# Sheet1.net
KiCad netlist of a schematic drawn in Altium Designer
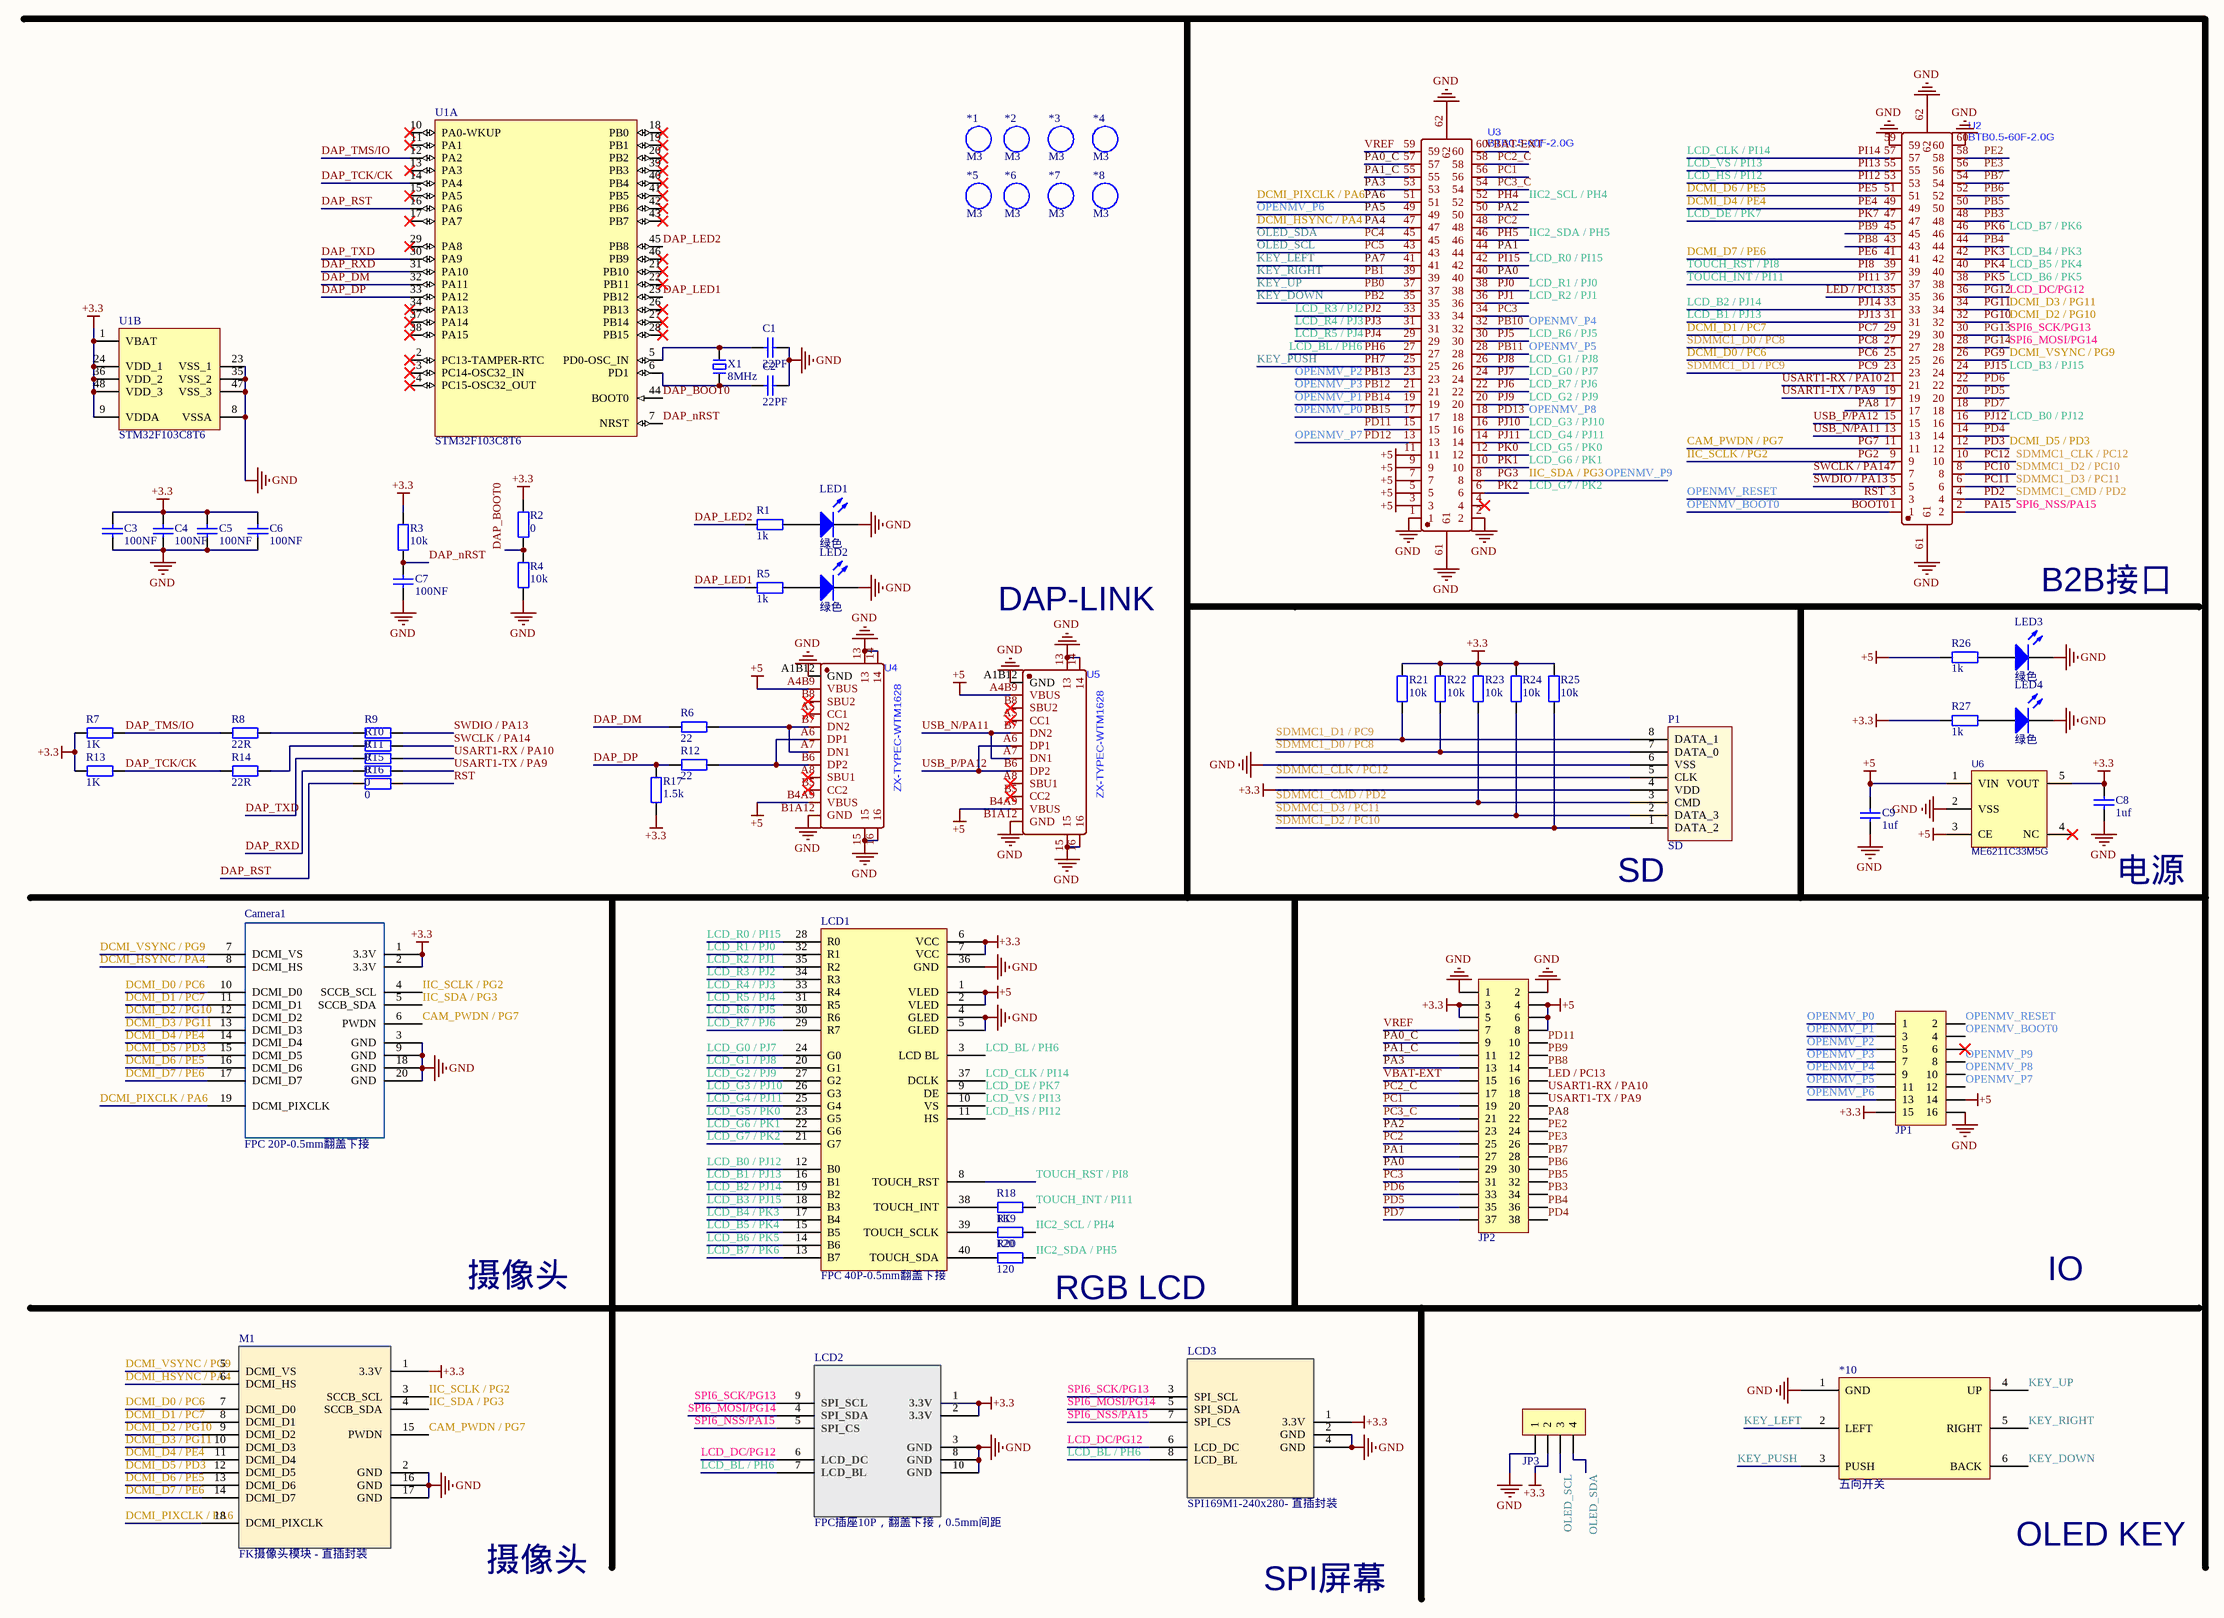
[diagram p0: Sheet1.SchDoc]

(export (version "E")
  (design (tool "Eeschema 10.0.6"))
  (components
    (comp (ref "*1")
      (value "M3")
      (footprint "PCB1:M3 125X200")
      (description "铜柱孔")
      (libsource (lib "STM32H750底板") (part "M3"))
    )
    (comp (ref "*2")
      (value "M3")
      (footprint "PCB1:M3 125X200")
      (description "铜柱孔")
      (libsource (lib "STM32H750底板") (part "M3"))
    )
    (comp (ref "*3")
      (value "M3")
      (footprint "PCB1:M3 125X200")
      (description "铜柱孔")
      (libsource (lib "STM32H750底板") (part "M3"))
    )
    (comp (ref "*4")
      (value "M3")
      (footprint "PCB1:M3 125X200")
      (description "铜柱孔")
      (libsource (lib "STM32H750底板") (part "M3"))
    )
    (comp (ref "*5")
      (value "M3")
      (footprint "PCB1:M3 125X200")
      (description "铜柱孔")
      (libsource (lib "STM32H750底板") (part "M3"))
    )
    (comp (ref "*6")
      (value "M3")
      (footprint "PCB1:M3 125X200")
      (description "铜柱孔")
      (libsource (lib "STM32H750底板") (part "M3"))
    )
    (comp (ref "*7")
      (value "M3")
      (footprint "PCB1:M3 125X200")
      (description "铜柱孔")
      (libsource (lib "STM32H750底板") (part "M3"))
    )
    (comp (ref "*8")
      (value "M3")
      (footprint "PCB1:M3 125X200")
      (description "铜柱孔")
      (libsource (lib "STM32H750底板") (part "M3"))
    )
    (comp (ref "*10")
      (value "五向开关")
      (footprint "PCB1:PCBComponent_1 - duplicate")
      (libsource (lib "STM32H750底板") (part "五向开关"))
    )
    (comp (ref "C1")
      (value "22PF")
      (footprint "PCB1:C0603_L")
      (description "贴片电容/MLCC电容")
      (libsource (lib "STM32H750底板") (part "C"))
    )
    (comp (ref "C2")
      (value "22PF")
      (footprint "PCB1:C0603_L")
      (description "贴片电容/MLCC电容")
      (libsource (lib "STM32H750底板") (part "C"))
    )
    (comp (ref "C3")
      (value "100NF")
      (footprint "PCB1:C0603_L")
      (description "贴片电容/MLCC电容")
      (libsource (lib "STM32H750底板") (part "C"))
    )
    (comp (ref "C4")
      (value "100NF")
      (footprint "PCB1:C0603_L")
      (description "贴片电容/MLCC电容")
      (libsource (lib "STM32H750底板") (part "C"))
    )
    (comp (ref "C5")
      (value "100NF")
      (footprint "PCB1:C0603_L")
      (description "贴片电容/MLCC电容")
      (libsource (lib "STM32H750底板") (part "C"))
    )
    (comp (ref "C6")
      (value "100NF")
      (footprint "PCB1:C0603_L")
      (description "贴片电容/MLCC电容")
      (libsource (lib "STM32H750底板") (part "C"))
    )
    (comp (ref "C7")
      (value "100NF")
      (footprint "PCB1:C0603_L")
      (description "贴片电容/MLCC电容")
      (libsource (lib "STM32H750底板") (part "C"))
    )
    (comp (ref "C8")
      (value "1uf")
      (footprint "PCB1:C0603_L")
      (description "贴片电容/MLCC电容")
      (libsource (lib "STM32H750底板") (part "C"))
    )
    (comp (ref "C9")
      (value "1uf")
      (footprint "PCB1:C0603_L")
      (description "贴片电容/MLCC电容")
      (libsource (lib "STM32H750底板") (part "C"))
    )
    (comp (ref "Camera1")
      (value "FPC 20P-0.5mm翻盖下接")
      (footprint "PCB1:FPC20P-0.5MM")
      (libsource (lib "STM32H750底板") (part "FK_Camera"))
    )
    (comp (ref "JP1")
      (value "Header 8X2")
      (footprint "PCB1:HDR2.54-LI-2x8P")
      (description "8*2P接插件")
      (libsource (lib "STM32H750底板") (part "Header 8X2"))
    )
    (comp (ref "JP2")
      (value "Header 2X11")
      (footprint "PCB1:HDR2.54-LI-2x19P")
      (description "19*2P接插件")
      (libsource (lib "STM32H750底板") (part "Header 19X2"))
    )
    (comp (ref "JP3")
      (value "HDR-1X4")
      (footprint "PCB1:HDR2.54-LI-4P")
      (description "4P接插件")
      (libsource (lib "STM32H750底板") (part "Header 4"))
    )
    (comp (ref "LCD1")
      (value "FPC 40P-0.5mm翻盖下接")
      (footprint "PCB1:FPC40P-0.5MM")
      (libsource (lib "STM32H750底板") (part "MY-RGB"))
    )
    (comp (ref "LCD2")
      (value "FPC插座10P，翻盖下接，0.5mm间距")
      (footprint "PCB1:FPC10P-0.5MM")
      (libsource (lib "STM32H750底板") (part "LCD-SPI"))
    )
    (comp (ref "LCD3")
      (value "SPI169M1-240x280- 直插封装")
      (footprint "PCB1:SPI169M1-240x280 - 直插封装")
      (libsource (lib "STM32H750底板") (part "SPI169M1-240x280- 直插封装"))
    )
    (comp (ref "LED1")
      (value "绿色")
      (footprint "PCB1:LED0805_G")
      (description "贴片LED")
      (libsource (lib "STM32H750底板") (part "LED"))
    )
    (comp (ref "LED2")
      (value "绿色")
      (footprint "PCB1:LED0805_G")
      (description "贴片LED")
      (libsource (lib "STM32H750底板") (part "LED"))
    )
    (comp (ref "LED3")
      (value "绿色")
      (footprint "PCB1:LED0805_G")
      (description "贴片LED")
      (libsource (lib "STM32H750底板") (part "LED"))
    )
    (comp (ref "LED4")
      (value "绿色")
      (footprint "PCB1:LED0805_G")
      (description "贴片LED")
      (libsource (lib "STM32H750底板") (part "LED"))
    )
    (comp (ref "M1") (value "FK摄像头模块 - 直插封装") (libsource (lib "STM32H750底板") (part "FK摄像头模块 - 直插封装")))
    (comp (ref "P1")
      (value "SD")
      (footprint "PCB1:MICRO SD")
      (description "自弹式TF卡座")
      (libsource (lib "STM32H750底板") (part "Micro SD_SD"))
    )
    (comp (ref "R1")
      (value "1k")
      (footprint "PCB1:R0603_L")
      (description "贴片电阻")
      (libsource (lib "STM32H750底板") (part "R"))
    )
    (comp (ref "R2")
      (value "0")
      (footprint "PCB1:R0603_L")
      (description "贴片电阻")
      (libsource (lib "STM32H750底板") (part "R"))
    )
    (comp (ref "R3")
      (value "10k")
      (footprint "PCB1:R0603_L")
      (description "贴片电阻")
      (libsource (lib "STM32H750底板") (part "R"))
    )
    (comp (ref "R4")
      (value "10k")
      (footprint "PCB1:R0603_L")
      (description "贴片电阻")
      (libsource (lib "STM32H750底板") (part "R"))
    )
    (comp (ref "R5")
      (value "1k")
      (footprint "PCB1:R0603_L")
      (description "贴片电阻")
      (libsource (lib "STM32H750底板") (part "R"))
    )
    (comp (ref "R6")
      (value "22")
      (footprint "PCB1:R0402_L")
      (description "贴片电阻")
      (libsource (lib "STM32H750底板") (part "R"))
    )
    (comp (ref "R7")
      (value "1K")
      (footprint "PCB1:R0603_L")
      (description "贴片电阻")
      (libsource (lib "STM32H750底板") (part "R"))
    )
    (comp (ref "R8")
      (value "22R")
      (footprint "PCB1:R0603_L")
      (description "贴片电阻")
      (libsource (lib "STM32H750底板") (part "R"))
    )
    (comp (ref "R9")
      (value "0")
      (footprint "PCB1:R0603_L")
      (description "贴片电阻")
      (libsource (lib "STM32H750底板") (part "R"))
    )
    (comp (ref "R10")
      (value "0")
      (footprint "PCB1:R0603_L")
      (description "贴片电阻")
      (libsource (lib "STM32H750底板") (part "R"))
    )
    (comp (ref "R11")
      (value "0")
      (footprint "PCB1:R0603_L")
      (description "贴片电阻")
      (libsource (lib "STM32H750底板") (part "R"))
    )
    (comp (ref "R12")
      (value "22")
      (footprint "PCB1:R0402_L")
      (description "贴片电阻")
      (libsource (lib "STM32H750底板") (part "R"))
    )
    (comp (ref "R13")
      (value "1K")
      (footprint "PCB1:R0603_L")
      (description "贴片电阻")
      (libsource (lib "STM32H750底板") (part "R"))
    )
    (comp (ref "R14")
      (value "22R")
      (footprint "PCB1:R0603_L")
      (description "贴片电阻")
      (libsource (lib "STM32H750底板") (part "R"))
    )
    (comp (ref "R15")
      (value "0")
      (footprint "PCB1:R0603_L")
      (description "贴片电阻")
      (libsource (lib "STM32H750底板") (part "R"))
    )
    (comp (ref "R16")
      (value "0")
      (footprint "PCB1:R0603_L")
      (description "贴片电阻")
      (libsource (lib "STM32H750底板") (part "R"))
    )
    (comp (ref "R17")
      (value "1.5k")
      (footprint "PCB1:R0402_L")
      (description "贴片电阻")
      (libsource (lib "STM32H750底板") (part "R"))
    )
    (comp (ref "R18")
      (value "1K")
      (footprint "PCB1:R0603_L")
      (description "贴片电阻")
      (libsource (lib "STM32H750底板") (part "R"))
    )
    (comp (ref "R19")
      (value "120")
      (footprint "PCB1:R0603_L")
      (description "贴片电阻")
      (libsource (lib "STM32H750底板") (part "R"))
    )
    (comp (ref "R20")
      (value "120")
      (footprint "PCB1:R0603_L")
      (description "贴片电阻")
      (libsource (lib "STM32H750底板") (part "R"))
    )
    (comp (ref "R21")
      (value "10k")
      (footprint "PCB1:R0603_L")
      (description "贴片电阻")
      (libsource (lib "STM32H750底板") (part "R"))
    )
    (comp (ref "R22")
      (value "10k")
      (footprint "PCB1:R0603_L")
      (description "贴片电阻")
      (libsource (lib "STM32H750底板") (part "R"))
    )
    (comp (ref "R23")
      (value "10k")
      (footprint "PCB1:R0603_L")
      (description "贴片电阻")
      (libsource (lib "STM32H750底板") (part "R"))
    )
    (comp (ref "R24")
      (value "10k")
      (footprint "PCB1:R0603_L")
      (description "贴片电阻")
      (libsource (lib "STM32H750底板") (part "R"))
    )
    (comp (ref "R25")
      (value "10k")
      (footprint "PCB1:R0603_L")
      (description "贴片电阻")
      (libsource (lib "STM32H750底板") (part "R"))
    )
    (comp (ref "R26")
      (value "1k")
      (footprint "PCB1:R0603_L")
      (description "贴片电阻")
      (libsource (lib "STM32H750底板") (part "R"))
    )
    (comp (ref "R27")
      (value "1k")
      (footprint "PCB1:R0603_L")
      (description "贴片电阻")
      (libsource (lib "STM32H750底板") (part "R"))
    )
    (comp (ref "U1")
      (value "STM32F103C8T6")
      (footprint "PCB1:LQFP48_N")
      (libsource (lib "STM32H750底板") (part "STM32F103C8T6"))
    )
    (comp (ref "U2")
      (value "BTB0.5-60F-2.0G")
      (footprint "PCB1:CONN-SMD_60P-P0.50_BTB0.5-60F-2.0G")
      (libsource (lib "STM32H750底板") (part "BTB0.5-60F-2.0G"))
    )
    (comp (ref "U3")
      (value "BTB0.5-60F-2.0G")
      (footprint "PCB1:CONN-SMD_60P-P0.50_BTB0.5-60F-2.0G")
      (libsource (lib "STM32H750底板") (part "BTB0.5-60F-2.0G"))
    )
    (comp (ref "U4")
      (value "ZX-TYPEC-WTM1628")
      (footprint "PCB1:USB-C-SMD_ZX-TYPEC-WTM1628")
      (libsource (lib "STM32H750底板") (part "ZX-TYPEC-WTM1628"))
    )
    (comp (ref "U5")
      (value "ZX-TYPEC-WTM1628")
      (footprint "PCB1:USB-C-SMD_ZX-TYPEC-WTM1628")
      (libsource (lib "STM32H750底板") (part "ZX-TYPEC-WTM1628"))
    )
    (comp (ref "U6")
      (value "ME6211C33M5G")
      (footprint "PCB1:SOT-23-5")
      (description "LDO 3.3V/0.5A")
      (libsource (lib "STM32H750底板") (part "ME6211C33"))
    )
    (comp (ref "X1")
      (value "8MHz")
      (footprint "PCB1:XTAL-3215-2P")
      (description "2脚无源晶振(谐振器）")
      (libsource (lib "STM32H750底板") (part "XTAL-2P"))
    )
  )
  (nets
    (net (code "1") (name "+3.3") (class "Default")
      (node (ref "C3") (pin "2") (pinfunction "2_2") (pintype "passive"))
      (node (ref "C4") (pin "2") (pinfunction "2_2") (pintype "passive"))
      (node (ref "C5") (pin "2") (pinfunction "2_2") (pintype "passive"))
      (node (ref "C6") (pin "2") (pinfunction "2_2") (pintype "passive"))
      (node (ref "C8") (pin "2") (pinfunction "2_2") (pintype "passive"))
      (node (ref "Camera1") (pin "1") (pinfunction "3.3V_1") (pintype "passive"))
      (node (ref "Camera1") (pin "2") (pinfunction "3.3V_2") (pintype "passive"))
      (node (ref "JP1") (pin "15") (pinfunction "15_15") (pintype "passive"))
      (node (ref "JP2") (pin "3") (pinfunction "3_3") (pintype "passive"))
      (node (ref "JP2") (pin "5") (pinfunction "5_5") (pintype "passive"))
      (node (ref "JP3") (pin "2") (pinfunction "2_2") (pintype "passive"))
      (node (ref "LCD1") (pin "6") (pinfunction "VCC_6") (pintype "passive"))
      (node (ref "LCD1") (pin "7") (pinfunction "VCC_7") (pintype "passive"))
      (node (ref "LCD2") (pin "1") (pinfunction "3.3V_1") (pintype "passive"))
      (node (ref "LCD2") (pin "2") (pinfunction "3.3V_2") (pintype "passive"))
      (node (ref "LCD3") (pin "1") (pinfunction "3.3V_1") (pintype "passive"))
      (node (ref "M1") (pin "1") (pinfunction "3.3V_1") (pintype "passive"))
      (node (ref "P1") (pin "4") (pinfunction "VDD_4") (pintype "passive"))
      (node (ref "R13") (pin "1") (pinfunction "1_1") (pintype "passive"))
      (node (ref "R17") (pin "1") (pinfunction "1_1") (pintype "passive"))
      (node (ref "R2") (pin "2") (pinfunction "2_2") (pintype "passive"))
      (node (ref "R21") (pin "1") (pinfunction "1_1") (pintype "passive"))
      (node (ref "R22") (pin "1") (pinfunction "1_1") (pintype "passive"))
      (node (ref "R23") (pin "1") (pinfunction "1_1") (pintype "passive"))
      (node (ref "R24") (pin "1") (pinfunction "1_1") (pintype "passive"))
      (node (ref "R25") (pin "1") (pinfunction "1_1") (pintype "passive"))
      (node (ref "R27") (pin "1") (pinfunction "1_1") (pintype "passive"))
      (node (ref "R3") (pin "2") (pinfunction "2_2") (pintype "passive"))
      (node (ref "R7") (pin "1") (pinfunction "1_1") (pintype "passive"))
      (node (ref "U1") (pin "1") (pinfunction "VBAT_1") (pintype "power_in"))
      (node (ref "U1") (pin "24") (pinfunction "VDD_1_24") (pintype "power_in"))
      (node (ref "U1") (pin "36") (pinfunction "VDD_2_36") (pintype "power_in"))
      (node (ref "U1") (pin "48") (pinfunction "VDD_3_48") (pintype "power_in"))
      (node (ref "U1") (pin "9") (pinfunction "VDDA_9") (pintype "power_in"))
      (node (ref "U6") (pin "5") (pinfunction "VOUT_5") (pintype "passive"))
    )
    (net (code "2") (name "+5") (class "Default")
      (node (ref "C9") (pin "2") (pinfunction "2_2") (pintype "passive"))
      (node (ref "JP1") (pin "14") (pinfunction "14_14") (pintype "passive"))
      (node (ref "JP2") (pin "4") (pinfunction "4_4") (pintype "passive"))
      (node (ref "JP2") (pin "6") (pinfunction "6_6") (pintype "passive"))
      (node (ref "JP2") (pin "8") (pinfunction "8_8") (pintype "passive"))
      (node (ref "LCD1") (pin "1") (pinfunction "VLED_1") (pintype "passive"))
      (node (ref "LCD1") (pin "2") (pinfunction "VLED_2") (pintype "passive"))
      (node (ref "R26") (pin "1") (pinfunction "1_1") (pintype "passive"))
      (node (ref "U3") (pin "11") (pinfunction "11_11") (pintype "passive"))
      (node (ref "U3") (pin "3") (pinfunction "3_3") (pintype "passive"))
      (node (ref "U3") (pin "5") (pinfunction "5_5") (pintype "passive"))
      (node (ref "U3") (pin "7") (pinfunction "7_7") (pintype "passive"))
      (node (ref "U3") (pin "9") (pinfunction "9_9") (pintype "passive"))
      (node (ref "U4") (pin "A4B9") (pinfunction "VBUS_A4B9") (pintype "passive"))
      (node (ref "U4") (pin "B4A9") (pinfunction "VBUS_B4A9") (pintype "passive"))
      (node (ref "U5") (pin "A4B9") (pinfunction "VBUS_A4B9") (pintype "passive"))
      (node (ref "U5") (pin "B4A9") (pinfunction "VBUS_B4A9") (pintype "passive"))
      (node (ref "U6") (pin "1") (pinfunction "VIN_1") (pintype "passive"))
      (node (ref "U6") (pin "3") (pinfunction "CE_3") (pintype "passive"))
    )
    (net (code "3") (name "/BOOT0") (class "Default")
      (node (ref "JP1") (pin "4") (pinfunction "4_4") (pintype "passive"))
      (node (ref "U2") (pin "1") (pinfunction "1_1") (pintype "passive"))
    )
    (net (code "4") (name "/CAM_PWDN {slash} PG7") (class "Default")
      (node (ref "Camera1") (pin "6") (pinfunction "PWDN_6") (pintype "passive"))
      (node (ref "M1") (pin "15") (pinfunction "PWDN_15") (pintype "passive"))
      (node (ref "U2") (pin "11") (pinfunction "11_11") (pintype "passive"))
    )
    (net (code "5") (name "/DAP_BOOT0") (class "Default")
      (node (ref "R2") (pin "1") (pinfunction "1_1") (pintype "passive"))
      (node (ref "R4") (pin "2") (pinfunction "2_2") (pintype "passive"))
      (node (ref "U1") (pin "44") (pinfunction "BOOT0_44") (pintype "input"))
    )
    (net (code "6") (name "/DAP_DM") (class "Default")
      (node (ref "R6") (pin "1") (pinfunction "1_1") (pintype "passive"))
      (node (ref "U1") (pin "32") (pinfunction "PA11_32") (pintype "bidirectional"))
    )
    (net (code "7") (name "/DAP_DP") (class "Default")
      (node (ref "R12") (pin "1") (pinfunction "1_1") (pintype "passive"))
      (node (ref "R17") (pin "2") (pinfunction "2_2") (pintype "passive"))
      (node (ref "U1") (pin "33") (pinfunction "PA12_33") (pintype "bidirectional"))
    )
    (net (code "8") (name "/DAP_LED1") (class "Default")
      (node (ref "R5") (pin "1") (pinfunction "1_1") (pintype "passive"))
      (node (ref "U1") (pin "25") (pinfunction "PB12_25") (pintype "bidirectional"))
    )
    (net (code "9") (name "/DAP_LED2") (class "Default")
      (node (ref "R1") (pin "1") (pinfunction "1_1") (pintype "passive"))
      (node (ref "U1") (pin "45") (pinfunction "PB8_45") (pintype "bidirectional"))
    )
    (net (code "10") (name "/DAP_RST") (class "Default")
      (node (ref "R16") (pin "1") (pinfunction "1_1") (pintype "passive"))
      (node (ref "U1") (pin "16") (pinfunction "PA6_16") (pintype "bidirectional"))
    )
    (net (code "11") (name "/DAP_RXD") (class "Default")
      (node (ref "R15") (pin "1") (pinfunction "1_1") (pintype "passive"))
      (node (ref "U1") (pin "31") (pinfunction "PA10_31") (pintype "bidirectional"))
    )
    (net (code "12") (name "/DAP_TCK{slash}CK") (class "Default")
      (node (ref "R13") (pin "2") (pinfunction "2_2") (pintype "passive"))
      (node (ref "R14") (pin "1") (pinfunction "1_1") (pintype "passive"))
      (node (ref "U1") (pin "14") (pinfunction "PA4_14") (pintype "bidirectional"))
    )
    (net (code "13") (name "/DAP_TMS{slash}IO") (class "Default")
      (node (ref "R7") (pin "2") (pinfunction "2_2") (pintype "passive"))
      (node (ref "R8") (pin "1") (pinfunction "1_1") (pintype "passive"))
      (node (ref "U1") (pin "12") (pinfunction "PA2_12") (pintype "bidirectional"))
    )
    (net (code "14") (name "/DAP_TXD") (class "Default")
      (node (ref "R11") (pin "1") (pinfunction "1_1") (pintype "passive"))
      (node (ref "U1") (pin "30") (pinfunction "PA9_30") (pintype "bidirectional"))
    )
    (net (code "15") (name "/DAP_nRST") (class "Default")
      (node (ref "C7") (pin "2") (pinfunction "2_2") (pintype "passive"))
      (node (ref "R3") (pin "1") (pinfunction "1_1") (pintype "passive"))
      (node (ref "U1") (pin "7") (pinfunction "NRST_7") (pintype "bidirectional"))
    )
    (net (code "16") (name "/DCMI_D0 {slash} PC6") (class "Default")
      (node (ref "Camera1") (pin "10") (pinfunction "DCMI_D0_10") (pintype "passive"))
      (node (ref "M1") (pin "7") (pinfunction "DCMI_D0_7") (pintype "passive"))
      (node (ref "U2") (pin "25") (pinfunction "25_25") (pintype "passive"))
    )
    (net (code "17") (name "/DCMI_D1 {slash} PC7") (class "Default")
      (node (ref "Camera1") (pin "11") (pinfunction "DCMI_D1_11") (pintype "passive"))
      (node (ref "M1") (pin "8") (pinfunction "DCMI_D1_8") (pintype "passive"))
      (node (ref "U2") (pin "29") (pinfunction "29_29") (pintype "passive"))
    )
    (net (code "18") (name "/DCMI_D2 {slash} PG10") (class "Default")
      (node (ref "Camera1") (pin "12") (pinfunction "DCMI_D2_12") (pintype "passive"))
      (node (ref "M1") (pin "9") (pinfunction "DCMI_D2_9") (pintype "passive"))
      (node (ref "U2") (pin "32") (pinfunction "32_32") (pintype "passive"))
    )
    (net (code "19") (name "/DCMI_D3 {slash} PG11") (class "Default")
      (node (ref "Camera1") (pin "13") (pinfunction "DCMI_D3_13") (pintype "passive"))
      (node (ref "M1") (pin "10") (pinfunction "DCMI_D3_10") (pintype "passive"))
      (node (ref "U2") (pin "34") (pinfunction "34_34") (pintype "passive"))
    )
    (net (code "20") (name "/DCMI_D4 {slash} PE4") (class "Default")
      (node (ref "Camera1") (pin "14") (pinfunction "DCMI_D4_14") (pintype "passive"))
      (node (ref "M1") (pin "11") (pinfunction "DCMI_D4_11") (pintype "passive"))
      (node (ref "U2") (pin "49") (pinfunction "49_49") (pintype "passive"))
    )
    (net (code "21") (name "/DCMI_D5 {slash} PD3") (class "Default")
      (node (ref "Camera1") (pin "15") (pinfunction "DCMI_D5_15") (pintype "passive"))
      (node (ref "M1") (pin "12") (pinfunction "DCMI_D5_12") (pintype "passive"))
      (node (ref "U2") (pin "12") (pinfunction "12_12") (pintype "passive"))
    )
    (net (code "22") (name "/DCMI_D6 {slash} PE5") (class "Default")
      (node (ref "Camera1") (pin "16") (pinfunction "DCMI_D6_16") (pintype "passive"))
      (node (ref "M1") (pin "13") (pinfunction "DCMI_D6_13") (pintype "passive"))
      (node (ref "U2") (pin "51") (pinfunction "51_51") (pintype "passive"))
    )
    (net (code "23") (name "/DCMI_D7 {slash} PE6") (class "Default")
      (node (ref "Camera1") (pin "17") (pinfunction "DCMI_D7_17") (pintype "passive"))
      (node (ref "M1") (pin "14") (pinfunction "DCMI_D7_14") (pintype "passive"))
      (node (ref "U2") (pin "41") (pinfunction "41_41") (pintype "passive"))
    )
    (net (code "24") (name "/DCMI_HSYNC {slash} PA4") (class "Default")
      (node (ref "Camera1") (pin "8") (pinfunction "DCMI_HS_8") (pintype "passive"))
      (node (ref "M1") (pin "6") (pinfunction "DCMI_HS_6") (pintype "passive"))
      (node (ref "U3") (pin "47") (pinfunction "47_47") (pintype "passive"))
    )
    (net (code "25") (name "/DCMI_PIXCLK {slash} PA6") (class "Default")
      (node (ref "Camera1") (pin "19") (pinfunction "DCMI_PIXCLK_19") (pintype "passive"))
      (node (ref "M1") (pin "18") (pinfunction "DCMI_PIXCLK_18") (pintype "passive"))
      (node (ref "U3") (pin "51") (pinfunction "51_51") (pintype "passive"))
    )
    (net (code "26") (name "/DCMI_VSYNC {slash} PG9") (class "Default")
      (node (ref "Camera1") (pin "7") (pinfunction "DCMI_VS_7") (pintype "passive"))
      (node (ref "M1") (pin "5") (pinfunction "DCMI_VS_5") (pintype "passive"))
      (node (ref "U2") (pin "26") (pinfunction "26_26") (pintype "passive"))
    )
    (net (code "27") (name "/IIC2_SCL {slash} PH4") (class "Default")
      (node (ref "R19") (pin "2") (pinfunction "2_2") (pintype "passive"))
      (node (ref "U3") (pin "52") (pinfunction "52_52") (pintype "passive"))
    )
    (net (code "28") (name "/IIC2_SDA {slash} PH5") (class "Default")
      (node (ref "R20") (pin "2") (pinfunction "2_2") (pintype "passive"))
      (node (ref "U3") (pin "46") (pinfunction "46_46") (pintype "passive"))
    )
    (net (code "29") (name "/IIC_SCLK {slash} PG2") (class "Default")
      (node (ref "Camera1") (pin "4") (pinfunction "SCCB_SCL_4") (pintype "passive"))
      (node (ref "M1") (pin "3") (pinfunction "SCCB_SCL_3") (pintype "passive"))
      (node (ref "U2") (pin "9") (pinfunction "9_9") (pintype "passive"))
    )
    (net (code "30") (name "/IIC_SDA {slash} PG3") (class "Default")
      (node (ref "Camera1") (pin "5") (pinfunction "SCCB_SDA_5") (pintype "passive"))
      (node (ref "JP1") (pin "8") (pinfunction "8_8") (pintype "passive"))
      (node (ref "M1") (pin "4") (pinfunction "SCCB_SDA_4") (pintype "passive"))
      (node (ref "U3") (pin "8") (pinfunction "8_8") (pintype "passive"))
    )
    (net (code "31") (name "/KEY_DOWN") (class "Default")
      (node (ref "*10") (pin "6") (pinfunction "BACK_6") (pintype "passive"))
      (node (ref "U3") (pin "35") (pinfunction "35_35") (pintype "passive"))
    )
    (net (code "32") (name "/KEY_LEFT") (class "Default")
      (node (ref "*10") (pin "2") (pinfunction "LEFT_2") (pintype "passive"))
      (node (ref "U3") (pin "41") (pinfunction "41_41") (pintype "passive"))
    )
    (net (code "33") (name "/KEY_PUSH") (class "Default")
      (node (ref "*10") (pin "3") (pinfunction "PUSH_3") (pintype "passive"))
      (node (ref "U3") (pin "25") (pinfunction "25_25") (pintype "passive"))
    )
    (net (code "34") (name "/KEY_RIGHT") (class "Default")
      (node (ref "*10") (pin "5") (pinfunction "RIGHT_5") (pintype "passive"))
      (node (ref "U3") (pin "39") (pinfunction "39_39") (pintype "passive"))
    )
    (net (code "35") (name "/KEY_UP") (class "Default")
      (node (ref "*10") (pin "4") (pinfunction "UP_4") (pintype "passive"))
      (node (ref "U3") (pin "37") (pinfunction "37_37") (pintype "passive"))
    )
    (net (code "36") (name "/LCD_B0 {slash} PJ12") (class "Default")
      (node (ref "LCD1") (pin "12") (pinfunction "B0_12") (pintype "passive"))
      (node (ref "U2") (pin "16") (pinfunction "16_16") (pintype "passive"))
    )
    (net (code "37") (name "/LCD_B1 {slash} PJ13") (class "Default")
      (node (ref "LCD1") (pin "16") (pinfunction "B1_16") (pintype "passive"))
      (node (ref "U2") (pin "31") (pinfunction "31_31") (pintype "passive"))
    )
    (net (code "38") (name "/LCD_B2 {slash} PJ14") (class "Default")
      (node (ref "LCD1") (pin "19") (pinfunction "B2_19") (pintype "passive"))
      (node (ref "U2") (pin "33") (pinfunction "33_33") (pintype "passive"))
    )
    (net (code "39") (name "/LCD_B3 {slash} PJ15") (class "Default")
      (node (ref "LCD1") (pin "18") (pinfunction "B3_18") (pintype "passive"))
      (node (ref "U2") (pin "24") (pinfunction "24_24") (pintype "passive"))
    )
    (net (code "40") (name "/LCD_B4 {slash} PK3") (class "Default")
      (node (ref "LCD1") (pin "17") (pinfunction "B4_17") (pintype "passive"))
      (node (ref "U2") (pin "42") (pinfunction "42_42") (pintype "passive"))
    )
    (net (code "41") (name "/LCD_B5 {slash} PK4") (class "Default")
      (node (ref "LCD1") (pin "15") (pinfunction "B5_15") (pintype "passive"))
      (node (ref "U2") (pin "40") (pinfunction "40_40") (pintype "passive"))
    )
    (net (code "42") (name "/LCD_B6 {slash} PK5") (class "Default")
      (node (ref "LCD1") (pin "14") (pinfunction "B6_14") (pintype "passive"))
      (node (ref "U2") (pin "38") (pinfunction "38_38") (pintype "passive"))
    )
    (net (code "43") (name "/LCD_B7 {slash} PK6") (class "Default")
      (node (ref "LCD1") (pin "13") (pinfunction "B7_13") (pintype "passive"))
      (node (ref "U2") (pin "46") (pinfunction "46_46") (pintype "passive"))
    )
    (net (code "44") (name "/LCD_BL {slash} PH6") (class "Default")
      (node (ref "LCD1") (pin "3") (pinfunction "LCD_BL_3") (pintype "passive"))
      (node (ref "LCD2") (pin "7") (pinfunction "LCD_BL_7") (pintype "passive"))
      (node (ref "LCD3") (pin "8") (pinfunction "LCD_BL_8") (pintype "passive"))
      (node (ref "U3") (pin "27") (pinfunction "27_27") (pintype "passive"))
    )
    (net (code "45") (name "/LCD_CLK {slash} PI14") (class "Default")
      (node (ref "LCD1") (pin "37") (pinfunction "DCLK_37") (pintype "passive"))
      (node (ref "U2") (pin "57") (pinfunction "57_57") (pintype "passive"))
    )
    (net (code "46") (name "/LCD_DC{slash}PG12") (class "Default")
      (node (ref "LCD2") (pin "6") (pinfunction "LCD_DC_6") (pintype "passive"))
      (node (ref "LCD3") (pin "6") (pinfunction "LCD_DC_6") (pintype "passive"))
      (node (ref "U2") (pin "36") (pinfunction "36_36") (pintype "passive"))
    )
    (net (code "47") (name "/LCD_DE {slash} PK7") (class "Default")
      (node (ref "LCD1") (pin "9") (pinfunction "DE_9") (pintype "passive"))
      (node (ref "U2") (pin "47") (pinfunction "47_47") (pintype "passive"))
    )
    (net (code "48") (name "/LCD_G0 {slash} PJ7") (class "Default")
      (node (ref "LCD1") (pin "24") (pinfunction "G0_24") (pintype "passive"))
      (node (ref "U3") (pin "24") (pinfunction "24_24") (pintype "passive"))
    )
    (net (code "49") (name "/LCD_G1 {slash} PJ8") (class "Default")
      (node (ref "LCD1") (pin "20") (pinfunction "G1_20") (pintype "passive"))
      (node (ref "U3") (pin "26") (pinfunction "26_26") (pintype "passive"))
    )
    (net (code "50") (name "/LCD_G2 {slash} PJ9") (class "Default")
      (node (ref "LCD1") (pin "27") (pinfunction "G2_27") (pintype "passive"))
      (node (ref "U3") (pin "20") (pinfunction "20_20") (pintype "passive"))
    )
    (net (code "51") (name "/LCD_G3 {slash} PJ10") (class "Default")
      (node (ref "LCD1") (pin "26") (pinfunction "G3_26") (pintype "passive"))
      (node (ref "U3") (pin "16") (pinfunction "16_16") (pintype "passive"))
    )
    (net (code "52") (name "/LCD_G4 {slash} PJ11") (class "Default")
      (node (ref "LCD1") (pin "25") (pinfunction "G4_25") (pintype "passive"))
      (node (ref "U3") (pin "14") (pinfunction "14_14") (pintype "passive"))
    )
    (net (code "53") (name "/LCD_G5 {slash} PK0") (class "Default")
      (node (ref "LCD1") (pin "23") (pinfunction "G5_23") (pintype "passive"))
      (node (ref "U3") (pin "12") (pinfunction "12_12") (pintype "passive"))
    )
    (net (code "54") (name "/LCD_G6 {slash} PK1") (class "Default")
      (node (ref "LCD1") (pin "22") (pinfunction "G6_22") (pintype "passive"))
      (node (ref "U3") (pin "10") (pinfunction "10_10") (pintype "passive"))
    )
    (net (code "55") (name "/LCD_G7 {slash} PK2") (class "Default")
      (node (ref "LCD1") (pin "21") (pinfunction "G7_21") (pintype "passive"))
      (node (ref "U3") (pin "6") (pinfunction "6_6") (pintype "passive"))
    )
    (net (code "56") (name "/LCD_HS {slash} PI12") (class "Default")
      (node (ref "LCD1") (pin "11") (pinfunction "HS_11") (pintype "passive"))
      (node (ref "U2") (pin "53") (pinfunction "53_53") (pintype "passive"))
    )
    (net (code "57") (name "/LCD_R0 {slash} PI15") (class "Default")
      (node (ref "LCD1") (pin "28") (pinfunction "R0_28") (pintype "passive"))
      (node (ref "U3") (pin "42") (pinfunction "42_42") (pintype "passive"))
    )
    (net (code "58") (name "/LCD_R1 {slash} PJ0") (class "Default")
      (node (ref "LCD1") (pin "32") (pinfunction "R1_32") (pintype "passive"))
      (node (ref "U3") (pin "38") (pinfunction "38_38") (pintype "passive"))
    )
    (net (code "59") (name "/LCD_R2 {slash} PJ1") (class "Default")
      (node (ref "LCD1") (pin "35") (pinfunction "R2_35") (pintype "passive"))
      (node (ref "U3") (pin "36") (pinfunction "36_36") (pintype "passive"))
    )
    (net (code "60") (name "/LCD_R3 {slash} PJ2") (class "Default")
      (node (ref "LCD1") (pin "34") (pinfunction "R3_34") (pintype "passive"))
      (node (ref "U3") (pin "33") (pinfunction "33_33") (pintype "passive"))
    )
    (net (code "61") (name "/LCD_R4 {slash} PJ3") (class "Default")
      (node (ref "LCD1") (pin "33") (pinfunction "R4_33") (pintype "passive"))
      (node (ref "U3") (pin "31") (pinfunction "31_31") (pintype "passive"))
    )
    (net (code "62") (name "/LCD_R5 {slash} PJ4") (class "Default")
      (node (ref "LCD1") (pin "31") (pinfunction "R5_31") (pintype "passive"))
      (node (ref "U3") (pin "29") (pinfunction "29_29") (pintype "passive"))
    )
    (net (code "63") (name "/LCD_R6 {slash} PJ5") (class "Default")
      (node (ref "LCD1") (pin "30") (pinfunction "R6_30") (pintype "passive"))
      (node (ref "U3") (pin "30") (pinfunction "30_30") (pintype "passive"))
    )
    (net (code "64") (name "/LCD_R7 {slash} PJ6") (class "Default")
      (node (ref "LCD1") (pin "29") (pinfunction "R7_29") (pintype "passive"))
      (node (ref "U3") (pin "22") (pinfunction "22_22") (pintype "passive"))
    )
    (net (code "65") (name "/LCD_VS {slash} PI13") (class "Default")
      (node (ref "LCD1") (pin "10") (pinfunction "VS_10") (pintype "passive"))
      (node (ref "U2") (pin "55") (pinfunction "55_55") (pintype "passive"))
    )
    (net (code "66") (name "/LED {slash} PC13") (class "Default")
      (node (ref "JP2") (pin "16") (pinfunction "16_16") (pintype "passive"))
      (node (ref "U2") (pin "35") (pinfunction "35_35") (pintype "passive"))
    )
    (net (code "67") (name "/OLED_SCL") (class "Default")
      (node (ref "JP3") (pin "3") (pinfunction "3_3") (pintype "passive"))
      (node (ref "U3") (pin "43") (pinfunction "43_43") (pintype "passive"))
    )
    (net (code "68") (name "/OLED_SDA") (class "Default")
      (node (ref "JP3") (pin "4") (pinfunction "4_4") (pintype "passive"))
      (node (ref "U3") (pin "45") (pinfunction "45_45") (pintype "passive"))
    )
    (net (code "69") (name "/OPENMV_P0") (class "Default")
      (node (ref "JP1") (pin "1") (pinfunction "1_1") (pintype "passive"))
      (node (ref "U3") (pin "17") (pinfunction "17_17") (pintype "passive"))
    )
    (net (code "70") (name "/OPENMV_P1") (class "Default")
      (node (ref "JP1") (pin "3") (pinfunction "3_3") (pintype "passive"))
      (node (ref "U3") (pin "19") (pinfunction "19_19") (pintype "passive"))
    )
    (net (code "71") (name "/OPENMV_P2") (class "Default")
      (node (ref "JP1") (pin "5") (pinfunction "5_5") (pintype "passive"))
      (node (ref "U3") (pin "23") (pinfunction "23_23") (pintype "passive"))
    )
    (net (code "72") (name "/OPENMV_P3") (class "Default")
      (node (ref "JP1") (pin "7") (pinfunction "7_7") (pintype "passive"))
      (node (ref "U3") (pin "21") (pinfunction "21_21") (pintype "passive"))
    )
    (net (code "73") (name "/OPENMV_P4") (class "Default")
      (node (ref "JP1") (pin "9") (pinfunction "9_9") (pintype "passive"))
      (node (ref "U3") (pin "32") (pinfunction "32_32") (pintype "passive"))
    )
    (net (code "74") (name "/OPENMV_P5") (class "Default")
      (node (ref "JP1") (pin "11") (pinfunction "11_11") (pintype "passive"))
      (node (ref "U3") (pin "28") (pinfunction "28_28") (pintype "passive"))
    )
    (net (code "75") (name "/OPENMV_P6") (class "Default")
      (node (ref "JP1") (pin "13") (pinfunction "13_13") (pintype "passive"))
      (node (ref "U3") (pin "49") (pinfunction "49_49") (pintype "passive"))
    )
    (net (code "76") (name "/OPENMV_P7") (class "Default")
      (node (ref "JP1") (pin "12") (pinfunction "12_12") (pintype "passive"))
      (node (ref "U3") (pin "13") (pinfunction "13_13") (pintype "passive"))
    )
    (net (code "77") (name "/OPENMV_P8") (class "Default")
      (node (ref "JP1") (pin "10") (pinfunction "10_10") (pintype "passive"))
      (node (ref "U3") (pin "18") (pinfunction "18_18") (pintype "passive"))
    )
    (net (code "78") (name "/OPENMV_RESET") (class "Default")
      (node (ref "JP1") (pin "2") (pinfunction "2_2") (pintype "passive"))
      (node (ref "R16") (pin "2") (pinfunction "2_2") (pintype "passive"))
      (node (ref "U2") (pin "3") (pinfunction "3_3") (pintype "passive"))
    )
    (net (code "79") (name "/PA0") (class "Default")
      (node (ref "JP2") (pin "29") (pinfunction "29_29") (pintype "passive"))
      (node (ref "U3") (pin "40") (pinfunction "40_40") (pintype "passive"))
    )
    (net (code "80") (name "/PA0_C") (class "Default")
      (node (ref "JP2") (pin "9") (pinfunction "9_9") (pintype "passive"))
      (node (ref "U3") (pin "57") (pinfunction "57_57") (pintype "passive"))
    )
    (net (code "81") (name "/PA1") (class "Default")
      (node (ref "JP2") (pin "27") (pinfunction "27_27") (pintype "passive"))
      (node (ref "U3") (pin "44") (pinfunction "44_44") (pintype "passive"))
    )
    (net (code "82") (name "/PA1_C") (class "Default")
      (node (ref "JP2") (pin "11") (pinfunction "11_11") (pintype "passive"))
      (node (ref "U3") (pin "55") (pinfunction "55_55") (pintype "passive"))
    )
    (net (code "83") (name "/PA2") (class "Default")
      (node (ref "JP2") (pin "23") (pinfunction "23_23") (pintype "passive"))
      (node (ref "U3") (pin "50") (pinfunction "50_50") (pintype "passive"))
    )
    (net (code "84") (name "/PA3") (class "Default")
      (node (ref "JP2") (pin "13") (pinfunction "13_13") (pintype "passive"))
      (node (ref "U3") (pin "53") (pinfunction "53_53") (pintype "passive"))
    )
    (net (code "85") (name "/PA8") (class "Default")
      (node (ref "JP2") (pin "22") (pinfunction "22_22") (pintype "passive"))
      (node (ref "U2") (pin "17") (pinfunction "17_17") (pintype "passive"))
    )
    (net (code "86") (name "/PA15") (class "Default")
      (node (ref "LCD2") (pin "5") (pinfunction "SPI_CS_5") (pintype "passive"))
      (node (ref "LCD3") (pin "7") (pinfunction "SPI_CS_7") (pintype "passive"))
      (node (ref "U2") (pin "2") (pinfunction "2_2") (pintype "passive"))
    )
    (net (code "87") (name "/PB3") (class "Default")
      (node (ref "JP2") (pin "34") (pinfunction "34_34") (pintype "passive"))
      (node (ref "U2") (pin "48") (pinfunction "48_48") (pintype "passive"))
    )
    (net (code "88") (name "/PB4") (class "Default")
      (node (ref "JP2") (pin "36") (pinfunction "36_36") (pintype "passive"))
      (node (ref "U2") (pin "44") (pinfunction "44_44") (pintype "passive"))
    )
    (net (code "89") (name "/PB5") (class "Default")
      (node (ref "JP2") (pin "32") (pinfunction "32_32") (pintype "passive"))
      (node (ref "U2") (pin "50") (pinfunction "50_50") (pintype "passive"))
    )
    (net (code "90") (name "/PB6") (class "Default")
      (node (ref "JP2") (pin "30") (pinfunction "30_30") (pintype "passive"))
      (node (ref "U2") (pin "52") (pinfunction "52_52") (pintype "passive"))
    )
    (net (code "91") (name "/PB7") (class "Default")
      (node (ref "JP2") (pin "28") (pinfunction "28_28") (pintype "passive"))
      (node (ref "U2") (pin "54") (pinfunction "54_54") (pintype "passive"))
    )
    (net (code "92") (name "/PB8") (class "Default")
      (node (ref "JP2") (pin "14") (pinfunction "14_14") (pintype "passive"))
      (node (ref "U2") (pin "43") (pinfunction "43_43") (pintype "passive"))
    )
    (net (code "93") (name "/PB9") (class "Default")
      (node (ref "JP2") (pin "12") (pinfunction "12_12") (pintype "passive"))
      (node (ref "U2") (pin "45") (pinfunction "45_45") (pintype "passive"))
    )
    (net (code "94") (name "/PC1") (class "Default")
      (node (ref "JP2") (pin "19") (pinfunction "19_19") (pintype "passive"))
      (node (ref "U3") (pin "56") (pinfunction "56_56") (pintype "passive"))
    )
    (net (code "95") (name "/PC2") (class "Default")
      (node (ref "JP2") (pin "25") (pinfunction "25_25") (pintype "passive"))
      (node (ref "U3") (pin "48") (pinfunction "48_48") (pintype "passive"))
    )
    (net (code "96") (name "/PC2_C") (class "Default")
      (node (ref "JP2") (pin "17") (pinfunction "17_17") (pintype "passive"))
      (node (ref "U3") (pin "58") (pinfunction "58_58") (pintype "passive"))
    )
    (net (code "97") (name "/PC3") (class "Default")
      (node (ref "JP2") (pin "31") (pinfunction "31_31") (pintype "passive"))
      (node (ref "U3") (pin "34") (pinfunction "34_34") (pintype "passive"))
    )
    (net (code "98") (name "/PC3_C") (class "Default")
      (node (ref "JP2") (pin "21") (pinfunction "21_21") (pintype "passive"))
      (node (ref "U3") (pin "54") (pinfunction "54_54") (pintype "passive"))
    )
    (net (code "99") (name "/PC8") (class "Default")
      (node (ref "P1") (pin "7") (pinfunction "DATA_0_7") (pintype "passive"))
      (node (ref "R22") (pin "2") (pinfunction "2_2") (pintype "passive"))
      (node (ref "U2") (pin "27") (pinfunction "27_27") (pintype "passive"))
    )
    (net (code "100") (name "/PC9") (class "Default")
      (node (ref "P1") (pin "8") (pinfunction "DATA_1_8") (pintype "passive"))
      (node (ref "R21") (pin "2") (pinfunction "2_2") (pintype "passive"))
      (node (ref "U2") (pin "23") (pinfunction "23_23") (pintype "passive"))
    )
    (net (code "101") (name "/PC10") (class "Default")
      (node (ref "P1") (pin "1") (pinfunction "DATA_2_1") (pintype "passive"))
      (node (ref "R25") (pin "2") (pinfunction "2_2") (pintype "passive"))
      (node (ref "U2") (pin "8") (pinfunction "8_8") (pintype "passive"))
    )
    (net (code "102") (name "/PC11") (class "Default")
      (node (ref "P1") (pin "2") (pinfunction "DATA_3_2") (pintype "passive"))
      (node (ref "R24") (pin "2") (pinfunction "2_2") (pintype "passive"))
      (node (ref "U2") (pin "6") (pinfunction "6_6") (pintype "passive"))
    )
    (net (code "103") (name "/PC12") (class "Default")
      (node (ref "P1") (pin "5") (pinfunction "CLK_5") (pintype "passive"))
      (node (ref "U2") (pin "10") (pinfunction "10_10") (pintype "passive"))
    )
    (net (code "104") (name "/PD2") (class "Default")
      (node (ref "P1") (pin "3") (pinfunction "CMD_3") (pintype "passive"))
      (node (ref "R23") (pin "2") (pinfunction "2_2") (pintype "passive"))
      (node (ref "U2") (pin "4") (pinfunction "4_4") (pintype "passive"))
    )
    (net (code "105") (name "/PD4") (class "Default")
      (node (ref "JP2") (pin "38") (pinfunction "38_38") (pintype "passive"))
      (node (ref "U2") (pin "14") (pinfunction "14_14") (pintype "passive"))
    )
    (net (code "106") (name "/PD5") (class "Default")
      (node (ref "JP2") (pin "35") (pinfunction "35_35") (pintype "passive"))
      (node (ref "U2") (pin "20") (pinfunction "20_20") (pintype "passive"))
    )
    (net (code "107") (name "/PD6") (class "Default")
      (node (ref "JP2") (pin "33") (pinfunction "33_33") (pintype "passive"))
      (node (ref "U2") (pin "22") (pinfunction "22_22") (pintype "passive"))
    )
    (net (code "108") (name "/PD7") (class "Default")
      (node (ref "JP2") (pin "37") (pinfunction "37_37") (pintype "passive"))
      (node (ref "U2") (pin "18") (pinfunction "18_18") (pintype "passive"))
    )
    (net (code "109") (name "/PD11") (class "Default")
      (node (ref "JP2") (pin "10") (pinfunction "10_10") (pintype "passive"))
      (node (ref "U3") (pin "15") (pinfunction "15_15") (pintype "passive"))
    )
    (net (code "110") (name "/PE2") (class "Default")
      (node (ref "JP2") (pin "24") (pinfunction "24_24") (pintype "passive"))
      (node (ref "U2") (pin "58") (pinfunction "58_58") (pintype "passive"))
    )
    (net (code "111") (name "/PE3") (class "Default")
      (node (ref "JP2") (pin "26") (pinfunction "26_26") (pintype "passive"))
      (node (ref "U2") (pin "56") (pinfunction "56_56") (pintype "passive"))
    )
    (net (code "112") (name "/PG13") (class "Default")
      (node (ref "LCD2") (pin "9") (pinfunction "SPI_SCL_9") (pintype "passive"))
      (node (ref "LCD3") (pin "3") (pinfunction "SPI_SCL_3") (pintype "passive"))
      (node (ref "U2") (pin "30") (pinfunction "30_30") (pintype "passive"))
    )
    (net (code "113") (name "/PG14") (class "Default")
      (node (ref "LCD2") (pin "4") (pinfunction "SPI_SDA_4") (pintype "passive"))
      (node (ref "LCD3") (pin "5") (pinfunction "SPI_SDA_5") (pintype "passive"))
      (node (ref "U2") (pin "28") (pinfunction "28_28") (pintype "passive"))
    )
    (net (code "114") (name "/PI8") (class "Default")
      (node (ref "LCD1") (pin "8") (pinfunction "TOUCH_RST_8") (pintype "passive"))
      (node (ref "U2") (pin "39") (pinfunction "39_39") (pintype "passive"))
    )
    (net (code "115") (name "/PI11") (class "Default")
      (node (ref "R18") (pin "2") (pinfunction "2_2") (pintype "passive"))
      (node (ref "U2") (pin "37") (pinfunction "37_37") (pintype "passive"))
    )
    (net (code "116") (name "/SWCLK {slash} PA14") (class "Default")
      (node (ref "R10") (pin "2") (pinfunction "2_2") (pintype "passive"))
      (node (ref "U2") (pin "7") (pinfunction "7_7") (pintype "passive"))
    )
    (net (code "117") (name "/SWDIO {slash} PA13") (class "Default")
      (node (ref "R9") (pin "2") (pinfunction "2_2") (pintype "passive"))
      (node (ref "U2") (pin "5") (pinfunction "5_5") (pintype "passive"))
    )
    (net (code "118") (name "/USART1-RX {slash} PA10") (class "Default")
      (node (ref "JP2") (pin "18") (pinfunction "18_18") (pintype "passive"))
      (node (ref "R11") (pin "2") (pinfunction "2_2") (pintype "passive"))
      (node (ref "U2") (pin "21") (pinfunction "21_21") (pintype "passive"))
    )
    (net (code "119") (name "/USART1-TX {slash} PA9") (class "Default")
      (node (ref "JP2") (pin "20") (pinfunction "20_20") (pintype "passive"))
      (node (ref "R15") (pin "2") (pinfunction "2_2") (pintype "passive"))
      (node (ref "U2") (pin "19") (pinfunction "19_19") (pintype "passive"))
    )
    (net (code "120") (name "/USB_N{slash}PA11") (class "Default")
      (node (ref "U2") (pin "13") (pinfunction "13_13") (pintype "passive"))
      (node (ref "U5") (pin "A7") (pinfunction "DN1_A7") (pintype "passive"))
      (node (ref "U5") (pin "B7") (pinfunction "DN2_B7") (pintype "passive"))
    )
    (net (code "121") (name "/USB_P{slash}PA12") (class "Default")
      (node (ref "U2") (pin "15") (pinfunction "15_15") (pintype "passive"))
      (node (ref "U5") (pin "A6") (pinfunction "DP1_A6") (pintype "passive"))
      (node (ref "U5") (pin "B6") (pinfunction "DP2_B6") (pintype "passive"))
    )
    (net (code "122") (name "/VBAT-EXT") (class "Default")
      (node (ref "JP2") (pin "15") (pinfunction "15_15") (pintype "passive"))
      (node (ref "U3") (pin "60") (pinfunction "60_60") (pintype "passive"))
    )
    (net (code "123") (name "/VREF") (class "Default")
      (node (ref "JP2") (pin "7") (pinfunction "7_7") (pintype "passive"))
      (node (ref "U3") (pin "59") (pinfunction "59_59") (pintype "passive"))
    )
    (net (code "124") (name "GND") (class "Default")
      (node (ref "*10") (pin "1") (pinfunction "GND_1") (pintype "passive"))
      (node (ref "C1") (pin "2") (pinfunction "2_2") (pintype "passive"))
      (node (ref "C2") (pin "2") (pinfunction "2_2") (pintype "passive"))
      (node (ref "C3") (pin "1") (pinfunction "1_1") (pintype "passive"))
      (node (ref "C4") (pin "1") (pinfunction "1_1") (pintype "passive"))
      (node (ref "C5") (pin "1") (pinfunction "1_1") (pintype "passive"))
      (node (ref "C6") (pin "1") (pinfunction "1_1") (pintype "passive"))
      (node (ref "C7") (pin "1") (pinfunction "1_1") (pintype "passive"))
      (node (ref "C8") (pin "1") (pinfunction "1_1") (pintype "passive"))
      (node (ref "C9") (pin "1") (pinfunction "1_1") (pintype "passive"))
      (node (ref "Camera1") (pin "18") (pinfunction "GND_18") (pintype "passive"))
      (node (ref "Camera1") (pin "20") (pinfunction "GND_20") (pintype "passive"))
      (node (ref "Camera1") (pin "3") (pinfunction "GND_3") (pintype "passive"))
      (node (ref "Camera1") (pin "9") (pinfunction "GND_9") (pintype "passive"))
      (node (ref "JP1") (pin "16") (pinfunction "16_16") (pintype "passive"))
      (node (ref "JP2") (pin "1") (pinfunction "1_1") (pintype "passive"))
      (node (ref "JP2") (pin "2") (pinfunction "2_2") (pintype "passive"))
      (node (ref "JP3") (pin "1") (pinfunction "1_1") (pintype "passive"))
      (node (ref "LCD1") (pin "36") (pinfunction "GND_36") (pintype "passive"))
      (node (ref "LCD1") (pin "4") (pinfunction "GLED_4") (pintype "passive"))
      (node (ref "LCD1") (pin "5") (pinfunction "GLED_5") (pintype "passive"))
      (node (ref "LCD2") (pin "10") (pinfunction "GND_10") (pintype "passive"))
      (node (ref "LCD2") (pin "3") (pinfunction "GND_3") (pintype "passive"))
      (node (ref "LCD2") (pin "8") (pinfunction "GND_8") (pintype "passive"))
      (node (ref "LCD3") (pin "2") (pinfunction "GND_2") (pintype "passive"))
      (node (ref "LCD3") (pin "4") (pinfunction "GND_4") (pintype "passive"))
      (node (ref "LED1") (pin "2") (pinfunction "K_2") (pintype "passive"))
      (node (ref "LED2") (pin "2") (pinfunction "K_2") (pintype "passive"))
      (node (ref "LED3") (pin "2") (pinfunction "K_2") (pintype "passive"))
      (node (ref "LED4") (pin "2") (pinfunction "K_2") (pintype "passive"))
      (node (ref "M1") (pin "16") (pinfunction "GND_16") (pintype "passive"))
      (node (ref "M1") (pin "17") (pinfunction "GND_17") (pintype "passive"))
      (node (ref "M1") (pin "2") (pinfunction "GND_2") (pintype "passive"))
      (node (ref "P1") (pin "6") (pinfunction "VSS_6") (pintype "passive"))
      (node (ref "R4") (pin "1") (pinfunction "1_1") (pintype "passive"))
      (node (ref "U1") (pin "23") (pinfunction "VSS_1_23") (pintype "power_in"))
      (node (ref "U1") (pin "35") (pinfunction "VSS_2_35") (pintype "power_in"))
      (node (ref "U1") (pin "47") (pinfunction "VSS_3_47") (pintype "power_in"))
      (node (ref "U1") (pin "8") (pinfunction "VSSA_8") (pintype "power_in"))
      (node (ref "U2") (pin "59") (pinfunction "59_59") (pintype "passive"))
      (node (ref "U2") (pin "60") (pinfunction "60_60") (pintype "passive"))
      (node (ref "U2") (pin "61") (pinfunction "61_61") (pintype "passive"))
      (node (ref "U2") (pin "62") (pinfunction "62_62") (pintype "passive"))
      (node (ref "U3") (pin "1") (pinfunction "1_1") (pintype "passive"))
      (node (ref "U3") (pin "2") (pinfunction "2_2") (pintype "passive"))
      (node (ref "U3") (pin "61") (pinfunction "61_61") (pintype "passive"))
      (node (ref "U3") (pin "62") (pinfunction "62_62") (pintype "passive"))
      (node (ref "U4") (pin "13") (pinfunction "13_13") (pintype "passive"))
      (node (ref "U4") (pin "14") (pinfunction "14_14") (pintype "passive"))
      (node (ref "U4") (pin "15") (pinfunction "15_15") (pintype "passive"))
      (node (ref "U4") (pin "16") (pinfunction "16_16") (pintype "passive"))
      (node (ref "U4") (pin "A1B12") (pinfunction "GND_A1B12") (pintype "passive"))
      (node (ref "U4") (pin "B1A12") (pinfunction "GND_B1A12") (pintype "passive"))
      (node (ref "U5") (pin "13") (pinfunction "13_13") (pintype "passive"))
      (node (ref "U5") (pin "14") (pinfunction "14_14") (pintype "passive"))
      (node (ref "U5") (pin "15") (pinfunction "15_15") (pintype "passive"))
      (node (ref "U5") (pin "16") (pinfunction "16_16") (pintype "passive"))
      (node (ref "U5") (pin "A1B12") (pinfunction "GND_A1B12") (pintype "passive"))
      (node (ref "U5") (pin "B1A12") (pinfunction "GND_B1A12") (pintype "passive"))
      (node (ref "U6") (pin "2") (pinfunction "VSS_2") (pintype "passive"))
    )
    (net (code "125") (name "Net-(LCD1-TOUCH_INT)") (class "Default")
      (node (ref "LCD1") (pin "38") (pinfunction "TOUCH_INT_38") (pintype "passive"))
      (node (ref "R18") (pin "1") (pinfunction "1_1") (pintype "passive"))
    )
    (net (code "126") (name "Net-(LCD1-TOUCH_SCLK)") (class "Default")
      (node (ref "LCD1") (pin "39") (pinfunction "TOUCH_SCLK_39") (pintype "passive"))
      (node (ref "R19") (pin "1") (pinfunction "1_1") (pintype "passive"))
    )
    (net (code "127") (name "Net-(LCD1-TOUCH_SDA)") (class "Default")
      (node (ref "LCD1") (pin "40") (pinfunction "TOUCH_SDA_40") (pintype "passive"))
      (node (ref "R20") (pin "1") (pinfunction "1_1") (pintype "passive"))
    )
    (net (code "128") (name "Net-(LED1-A)") (class "Default")
      (node (ref "LED1") (pin "1") (pinfunction "A_1") (pintype "passive"))
      (node (ref "R1") (pin "2") (pinfunction "2_2") (pintype "passive"))
    )
    (net (code "129") (name "Net-(LED2-A)") (class "Default")
      (node (ref "LED2") (pin "1") (pinfunction "A_1") (pintype "passive"))
      (node (ref "R5") (pin "2") (pinfunction "2_2") (pintype "passive"))
    )
    (net (code "130") (name "Net-(LED3-A)") (class "Default")
      (node (ref "LED3") (pin "1") (pinfunction "A_1") (pintype "passive"))
      (node (ref "R26") (pin "2") (pinfunction "2_2") (pintype "passive"))
    )
    (net (code "131") (name "Net-(LED4-A)") (class "Default")
      (node (ref "LED4") (pin "1") (pinfunction "A_1") (pintype "passive"))
      (node (ref "R27") (pin "2") (pinfunction "2_2") (pintype "passive"))
    )
    (net (code "132") (name "Net-(R8-Pad2)") (class "Default")
      (node (ref "R8") (pin "2") (pinfunction "2_2") (pintype "passive"))
      (node (ref "R9") (pin "1") (pinfunction "1_1") (pintype "passive"))
    )
    (net (code "133") (name "Net-(R10-Pad1)") (class "Default")
      (node (ref "R10") (pin "1") (pinfunction "1_1") (pintype "passive"))
      (node (ref "R14") (pin "2") (pinfunction "2_2") (pintype "passive"))
    )
    (net (code "134") (name "Net-(U1A-PD0-OSC_IN)") (class "Default")
      (node (ref "C1") (pin "1") (pinfunction "1_1") (pintype "passive"))
      (node (ref "U1") (pin "5") (pinfunction "PD0-OSC_IN_5") (pintype "bidirectional"))
      (node (ref "X1") (pin "1") (pinfunction "1_1") (pintype "passive"))
    )
    (net (code "135") (name "Net-(U1A-PD1)") (class "Default")
      (node (ref "C2") (pin "1") (pinfunction "1_1") (pintype "passive"))
      (node (ref "U1") (pin "6") (pinfunction "PD1_6") (pintype "bidirectional"))
      (node (ref "X1") (pin "2") (pinfunction "2_2") (pintype "passive"))
    )
    (net (code "136") (name "Net-(U4-DN1)") (class "Default")
      (node (ref "R6") (pin "2") (pinfunction "2_2") (pintype "passive"))
      (node (ref "U4") (pin "A7") (pinfunction "DN1_A7") (pintype "passive"))
      (node (ref "U4") (pin "B7") (pinfunction "DN2_B7") (pintype "passive"))
    )
    (net (code "137") (name "Net-(U4-DP1)") (class "Default")
      (node (ref "R12") (pin "2") (pinfunction "2_2") (pintype "passive"))
      (node (ref "U4") (pin "A6") (pinfunction "DP1_A6") (pintype "passive"))
      (node (ref "U4") (pin "B6") (pinfunction "DP2_B6") (pintype "passive"))
    )
    (net (code "138") (name "unconnected-(JP1-Pad6)") (class "Default")
      (node (ref "JP1") (pin "6") (pinfunction "6_6") (pintype "passive+no_connect"))
    )
    (net (code "139") (name "unconnected-(U1A-PA0-WKUP-Pad10)") (class "Default")
      (node (ref "U1") (pin "10") (pinfunction "PA0-WKUP_10") (pintype "bidirectional+no_connect"))
    )
    (net (code "140") (name "unconnected-(U1A-PA1-Pad11)") (class "Default")
      (node (ref "U1") (pin "11") (pinfunction "PA1_11") (pintype "bidirectional+no_connect"))
    )
    (net (code "141") (name "unconnected-(U1A-PA3-Pad13)") (class "Default")
      (node (ref "U1") (pin "13") (pinfunction "PA3_13") (pintype "bidirectional+no_connect"))
    )
    (net (code "142") (name "unconnected-(U1A-PA5-Pad15)") (class "Default")
      (node (ref "U1") (pin "15") (pinfunction "PA5_15") (pintype "bidirectional+no_connect"))
    )
    (net (code "143") (name "unconnected-(U1A-PA7-Pad17)") (class "Default")
      (node (ref "U1") (pin "17") (pinfunction "PA7_17") (pintype "bidirectional+no_connect"))
    )
    (net (code "144") (name "unconnected-(U1A-PA8-Pad29)") (class "Default")
      (node (ref "U1") (pin "29") (pinfunction "PA8_29") (pintype "bidirectional+no_connect"))
    )
    (net (code "145") (name "unconnected-(U1A-PA13-Pad34)") (class "Default")
      (node (ref "U1") (pin "34") (pinfunction "PA13_34") (pintype "bidirectional+no_connect"))
    )
    (net (code "146") (name "unconnected-(U1A-PA14-Pad37)") (class "Default")
      (node (ref "U1") (pin "37") (pinfunction "PA14_37") (pintype "bidirectional+no_connect"))
    )
    (net (code "147") (name "unconnected-(U1A-PA15-Pad38)") (class "Default")
      (node (ref "U1") (pin "38") (pinfunction "PA15_38") (pintype "bidirectional+no_connect"))
    )
    (net (code "148") (name "unconnected-(U1A-PB0-Pad18)") (class "Default")
      (node (ref "U1") (pin "18") (pinfunction "PB0_18") (pintype "bidirectional+no_connect"))
    )
    (net (code "149") (name "unconnected-(U1A-PB1-Pad19)") (class "Default")
      (node (ref "U1") (pin "19") (pinfunction "PB1_19") (pintype "bidirectional+no_connect"))
    )
    (net (code "150") (name "unconnected-(U1A-PB2-Pad20)") (class "Default")
      (node (ref "U1") (pin "20") (pinfunction "PB2_20") (pintype "bidirectional+no_connect"))
    )
    (net (code "151") (name "unconnected-(U1A-PB3-Pad39)") (class "Default")
      (node (ref "U1") (pin "39") (pinfunction "PB3_39") (pintype "bidirectional+no_connect"))
    )
    (net (code "152") (name "unconnected-(U1A-PB4-Pad40)") (class "Default")
      (node (ref "U1") (pin "40") (pinfunction "PB4_40") (pintype "bidirectional+no_connect"))
    )
    (net (code "153") (name "unconnected-(U1A-PB5-Pad41)") (class "Default")
      (node (ref "U1") (pin "41") (pinfunction "PB5_41") (pintype "bidirectional+no_connect"))
    )
    (net (code "154") (name "unconnected-(U1A-PB6-Pad42)") (class "Default")
      (node (ref "U1") (pin "42") (pinfunction "PB6_42") (pintype "bidirectional+no_connect"))
    )
    (net (code "155") (name "unconnected-(U1A-PB7-Pad43)") (class "Default")
      (node (ref "U1") (pin "43") (pinfunction "PB7_43") (pintype "bidirectional+no_connect"))
    )
    (net (code "156") (name "unconnected-(U1A-PB9-Pad46)") (class "Default")
      (node (ref "U1") (pin "46") (pinfunction "PB9_46") (pintype "bidirectional+no_connect"))
    )
    (net (code "157") (name "unconnected-(U1A-PB10-Pad21)") (class "Default")
      (node (ref "U1") (pin "21") (pinfunction "PB10_21") (pintype "bidirectional+no_connect"))
    )
    (net (code "158") (name "unconnected-(U1A-PB11-Pad22)") (class "Default")
      (node (ref "U1") (pin "22") (pinfunction "PB11_22") (pintype "bidirectional+no_connect"))
    )
    (net (code "159") (name "unconnected-(U1A-PB13-Pad26)") (class "Default")
      (node (ref "U1") (pin "26") (pinfunction "PB13_26") (pintype "bidirectional+no_connect"))
    )
    (net (code "160") (name "unconnected-(U1A-PB14-Pad27)") (class "Default")
      (node (ref "U1") (pin "27") (pinfunction "PB14_27") (pintype "bidirectional+no_connect"))
    )
    (net (code "161") (name "unconnected-(U1A-PB15-Pad28)") (class "Default")
      (node (ref "U1") (pin "28") (pinfunction "PB15_28") (pintype "bidirectional+no_connect"))
    )
    (net (code "162") (name "unconnected-(U1A-PC13-TAMPER-RTC-Pad2)") (class "Default")
      (node (ref "U1") (pin "2") (pinfunction "PC13-TAMPER-RTC_2") (pintype "bidirectional+no_connect"))
    )
    (net (code "163") (name "unconnected-(U1A-PC14-OSC32_IN-Pad3)") (class "Default")
      (node (ref "U1") (pin "3") (pinfunction "PC14-OSC32_IN_3") (pintype "bidirectional+no_connect"))
    )
    (net (code "164") (name "unconnected-(U1A-PC15-OSC32_OUT-Pad4)") (class "Default")
      (node (ref "U1") (pin "4") (pinfunction "PC15-OSC32_OUT_4") (pintype "bidirectional+no_connect"))
    )
    (net (code "165") (name "unconnected-(U3-Pad4)") (class "Default")
      (node (ref "U3") (pin "4") (pinfunction "4_4") (pintype "passive+no_connect"))
    )
    (net (code "166") (name "unconnected-(U4-CC1-PadA5)") (class "Default")
      (node (ref "U4") (pin "A5") (pinfunction "CC1_A5") (pintype "passive+no_connect"))
    )
    (net (code "167") (name "unconnected-(U4-CC2-PadB5)") (class "Default")
      (node (ref "U4") (pin "B5") (pinfunction "CC2_B5") (pintype "passive+no_connect"))
    )
    (net (code "168") (name "unconnected-(U4-SBU1-PadA8)") (class "Default")
      (node (ref "U4") (pin "A8") (pinfunction "SBU1_A8") (pintype "passive+no_connect"))
    )
    (net (code "169") (name "unconnected-(U4-SBU2-PadB8)") (class "Default")
      (node (ref "U4") (pin "B8") (pinfunction "SBU2_B8") (pintype "passive+no_connect"))
    )
    (net (code "170") (name "unconnected-(U5-CC1-PadA5)") (class "Default")
      (node (ref "U5") (pin "A5") (pinfunction "CC1_A5") (pintype "passive+no_connect"))
    )
    (net (code "171") (name "unconnected-(U5-CC2-PadB5)") (class "Default")
      (node (ref "U5") (pin "B5") (pinfunction "CC2_B5") (pintype "passive+no_connect"))
    )
    (net (code "172") (name "unconnected-(U5-SBU1-PadA8)") (class "Default")
      (node (ref "U5") (pin "A8") (pinfunction "SBU1_A8") (pintype "passive+no_connect"))
    )
    (net (code "173") (name "unconnected-(U5-SBU2-PadB8)") (class "Default")
      (node (ref "U5") (pin "B8") (pinfunction "SBU2_B8") (pintype "passive+no_connect"))
    )
    (net (code "174") (name "unconnected-(U6-NC-Pad4)") (class "Default")
      (node (ref "U6") (pin "4") (pinfunction "NC_4") (pintype "passive+no_connect"))
    )
  )
)
